# Power.net
KiCad netlist of a schematic drawn in Altium Designer
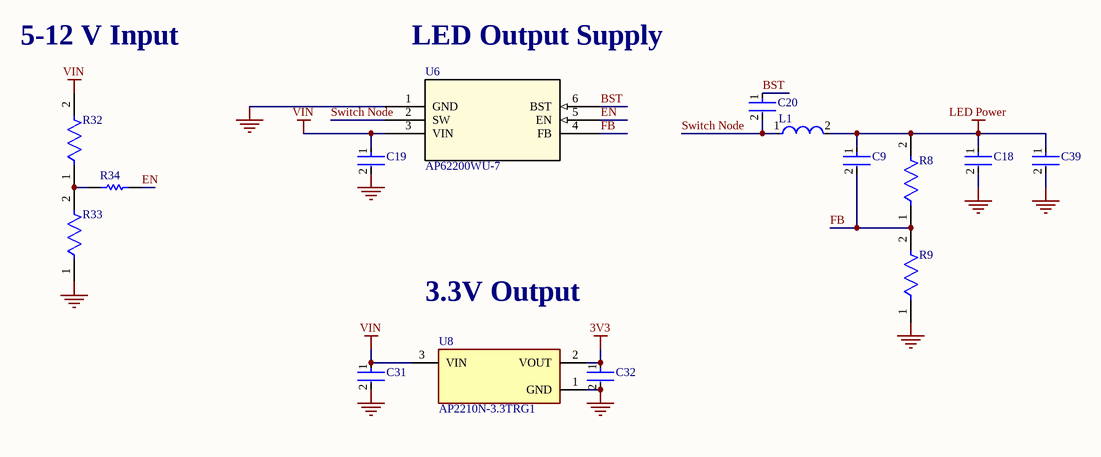
[diagram p0: Power.SchDoc]

(export (version "E")
  (design (tool "Eeschema 10.0.6"))
  (components
    (comp (ref "C9")
      (value "UMK105CG330JVHF")
      (footprint "FP-0402-L_1_0_0_05-W_0_5-MFG")
      (description "None")
      (fields (field (name "TOLERANCE") "5%"))
      (libsource (lib "Altium Content Vault") (part "b4654b650e69147ec39a6b967a45e02"))
    )
    (comp (ref "C18")
      (value "EMK316BB7226ML-T")
      (footprint "FP-1206-L_3_2_0_3-W_1_6_0-IPC_A")
      (description "None")
      (fields (field (name "TOLERANCE") "20%"))
      (libsource (lib "Altium Content Vault") (part "11868f565c42a9108669ba33697ecf6"))
    )
    (comp (ref "C19")
      (value "CL21A106KAYNNNE")
      (footprint "FP-CL21-IPC_A")
      (description "CL21 Series 0805 10uF 25V ±10% Tolerance X5R Multilayer Ceramic Chip Capacitor")
      (fields (field (name "TOLERANCE") "10%"))
      (libsource (lib "Altium Content Vault") (part "b4654b650e69147ec39a6b967a45e02"))
    )
    (comp (ref "C20")
      (value "GRM155R71C224KA12D")
      (footprint "FP-GRM155-0_05-IPC_C")
      (description "Chip Multilayer Ceramic Capacitors for General Purpose, 0402, 0.22uF, X7R, 15%, 10%, 16V")
      (fields (field (name "VOLTAGE") "16V") (field (name "TOLERANCE") "10%"))
      (libsource (lib "Altium Content Vault") (part "02cd4be3c70576c341d710602a673aa"))
    )
    (comp (ref "C31")
      (value "GCM21BR71H105MA03L")
      (footprint "FP-GCM21B-0_15-MFG")
      (description "Ceramic Capacitor for Automotive 1uF ±20% 50VDC X7R 0805 Embossed T/R")
      (libsource (lib "Altium Content Vault") (part "02cd4be3c70576c341d710602a673aa"))
    )
    (comp (ref "C32")
      (value "GCJ21BR71E225KA01L")
      (footprint "FP-GCJ21B-0_3-MFG")
      (description "Multilayer Ceramic Capacitors MLCC - SMD/SMT 0805 2.2uF 10%, 25VDC,  X7R 15%")
      (libsource (lib "Altium Content Vault") (part "02cd4be3c70576c341d710602a673aa"))
    )
    (comp (ref "C39")
      (value "EMK316BB7226ML-T")
      (footprint "FP-1206-L_3_2_0_3-W_1_6_0-IPC_A")
      (description "None")
      (fields (field (name "TOLERANCE") "20%"))
      (libsource (lib "Altium Content Vault") (part "11868f565c42a9108669ba33697ecf6"))
    )
    (comp (ref "L1")
      (value "LQM21PN4R7MGHL")
      (footprint "FP-LQM21PH_G0-IPC_B")
      (description "Multilayer Type Inductor for Power Lines, 0805 (2012), 4.7μH, 20%, 0.275Ω, 1.2A")
      (fields (field (name "TOLERANCE") "20%"))
      (libsource (lib "Altium Content Vault") (part "725321dda6339637d4d059423bc1c3c"))
    )
    (comp (ref "R8")
      (value "ESR10EZPF5232")
      (footprint "FP-ESR10-MFG")
      (description "52.3kΩ ±1% 0.4W 0805 Anti-Surge Chip Resistor AEC-Q200")
      (fields (field (name "TOLERANCE") "1%"))
      (libsource (lib "Altium Content Vault") (part "1029c3af85768c4190bb7ad29bc67b5"))
    )
    (comp (ref "R9")
      (value "AT0805DRE0710KL")
      (footprint "FP-AT0805-MFG")
      (description "Thin Film Chip Resistors Automotive Grade 10kΩ 0.5% 50ppm/°C 0805")
      (fields (field (name "TOLERANCE") "0.5%"))
      (libsource (lib "Altium Content Vault") (part "1029c3af85768c4190bb7ad29bc67b5"))
    )
    (comp (ref "R32")
      (value "AC0402JR-07200KL")
      (footprint "FP-AC0402-IPC_B")
      (description "RES 200kΩ ±5% 0.063W 0402")
      (fields (field (name "TOLERANCE") "5%"))
      (libsource (lib "Altium Content Vault") (part "1029c3af85768c4190bb7ad29bc67b5"))
    )
    (comp (ref "R33")
      (value "CRCW040250K0FKED")
      (footprint "FP-CRCW0402-e3-IPC_A")
      (description "RES Thick Film, 50kΩ, 1%, 0.063W, 100ppm/°C, 0402")
      (fields (field (name "TOLERANCE") "1%"))
      (libsource (lib "Altium Content Vault") (part "1029c3af85768c4190bb7ad29bc67b5"))
    )
    (comp (ref "R34")
      (value "RC0402JR-070RL")
      (footprint "RESC1005X40X25NL05T10")
      (description "RES 0 OHM JUMPER 1/16W 0402")
      (fields (field (name "MANUFACTURER") "Yageo / Phycomp"))
      (libsource (lib "Altium Content Vault") (part "RES"))
    )
    (comp (ref "U6")
      (value "AP62200WU-7")
      (footprint "TSOT26-WU_DIO")
      (description "No Description Available")
      (fields (field (name "COPYRIGHT") "Copyright (C) 2026 Ultra Librarian. All rights reserved."))
      (libsource (lib "AP62200WU-7") (part "AP62200WU-7"))
    )
    (comp (ref "U8")
      (value "AP2210N-3.3TRG1")
      (footprint "FP-SOT23-IPC_C")
      (description "IC REG LINEAR 3.3V 300MA SOT23-3")
      (libsource (lib "Altium Content Vault") (part "bd94623faa3c699494368a50adf163b"))
    )
  )
  (nets
    (net (code "1") (name "/BST") (class "Default")
      (node (ref "C20") (pin "1") (pinfunction "1_1") (pintype "passive"))
      (node (ref "U6") (pin "6") (pinfunction "BST_6") (pintype "input"))
    )
    (net (code "2") (name "/EN") (class "Default")
      (node (ref "R34") (pin "2") (pinfunction "2_2") (pintype "passive"))
      (node (ref "U6") (pin "5") (pinfunction "EN_5") (pintype "input"))
    )
    (net (code "3") (name "/FB") (class "Default")
      (node (ref "C9") (pin "2") (pinfunction "2_2") (pintype "passive"))
      (node (ref "R8") (pin "1") (pinfunction "1_1") (pintype "passive"))
      (node (ref "R9") (pin "2") (pinfunction "2_2") (pintype "passive"))
      (node (ref "U6") (pin "4") (pinfunction "FB_4") (pintype "passive"))
    )
    (net (code "4") (name "/Switch Node") (class "Default")
      (node (ref "C20") (pin "2") (pinfunction "2_2") (pintype "passive"))
      (node (ref "L1") (pin "1") (pinfunction "1_1") (pintype "passive"))
      (node (ref "U6") (pin "2") (pinfunction "SW_2") (pintype "passive"))
    )
    (net (code "5") (name "3V3") (class "Default")
      (node (ref "C32") (pin "1") (pinfunction "1_1") (pintype "passive"))
      (node (ref "U8") (pin "2") (pinfunction "VOUT_2") (pintype "power_in"))
    )
    (net (code "6") (name "GND") (class "Default")
      (node (ref "C18") (pin "2") (pinfunction "2_2") (pintype "passive"))
      (node (ref "C19") (pin "2") (pinfunction "2_2") (pintype "passive"))
      (node (ref "C31") (pin "2") (pinfunction "2_2") (pintype "passive"))
      (node (ref "C32") (pin "2") (pinfunction "2_2") (pintype "passive"))
      (node (ref "C39") (pin "2") (pinfunction "2_2") (pintype "passive"))
      (node (ref "R33") (pin "1") (pinfunction "1_1") (pintype "passive"))
      (node (ref "R9") (pin "1") (pinfunction "1_1") (pintype "passive"))
      (node (ref "U6") (pin "1") (pinfunction "GND_1") (pintype "power_in"))
      (node (ref "U8") (pin "1") (pinfunction "GND_1") (pintype "power_in"))
    )
    (net (code "7") (name "LED Power") (class "Default")
      (node (ref "C18") (pin "1") (pinfunction "1_1") (pintype "passive"))
      (node (ref "C39") (pin "1") (pinfunction "1_1") (pintype "passive"))
      (node (ref "C9") (pin "1") (pinfunction "1_1") (pintype "passive"))
      (node (ref "L1") (pin "2") (pinfunction "2_2") (pintype "passive"))
      (node (ref "R8") (pin "2") (pinfunction "2_2") (pintype "passive"))
    )
    (net (code "8") (name "Net-(R32-Pad1)") (class "Default")
      (node (ref "R32") (pin "1") (pinfunction "1_1") (pintype "passive"))
      (node (ref "R33") (pin "2") (pinfunction "2_2") (pintype "passive"))
      (node (ref "R34") (pin "1") (pinfunction "1_1") (pintype "passive"))
    )
    (net (code "9") (name "VIN") (class "Default")
      (node (ref "C19") (pin "1") (pinfunction "1_1") (pintype "passive"))
      (node (ref "C31") (pin "1") (pinfunction "1_1") (pintype "passive"))
      (node (ref "R32") (pin "2") (pinfunction "2_2") (pintype "passive"))
      (node (ref "U6") (pin "3") (pinfunction "VIN_3") (pintype "power_in"))
      (node (ref "U8") (pin "3") (pinfunction "VIN_3") (pintype "power_in"))
    )
  )
)
